# SCH_kxmx_kaugummi_4_0_2021-10-22.net
KiCad netlist of a schematic drawn in EasyEDA
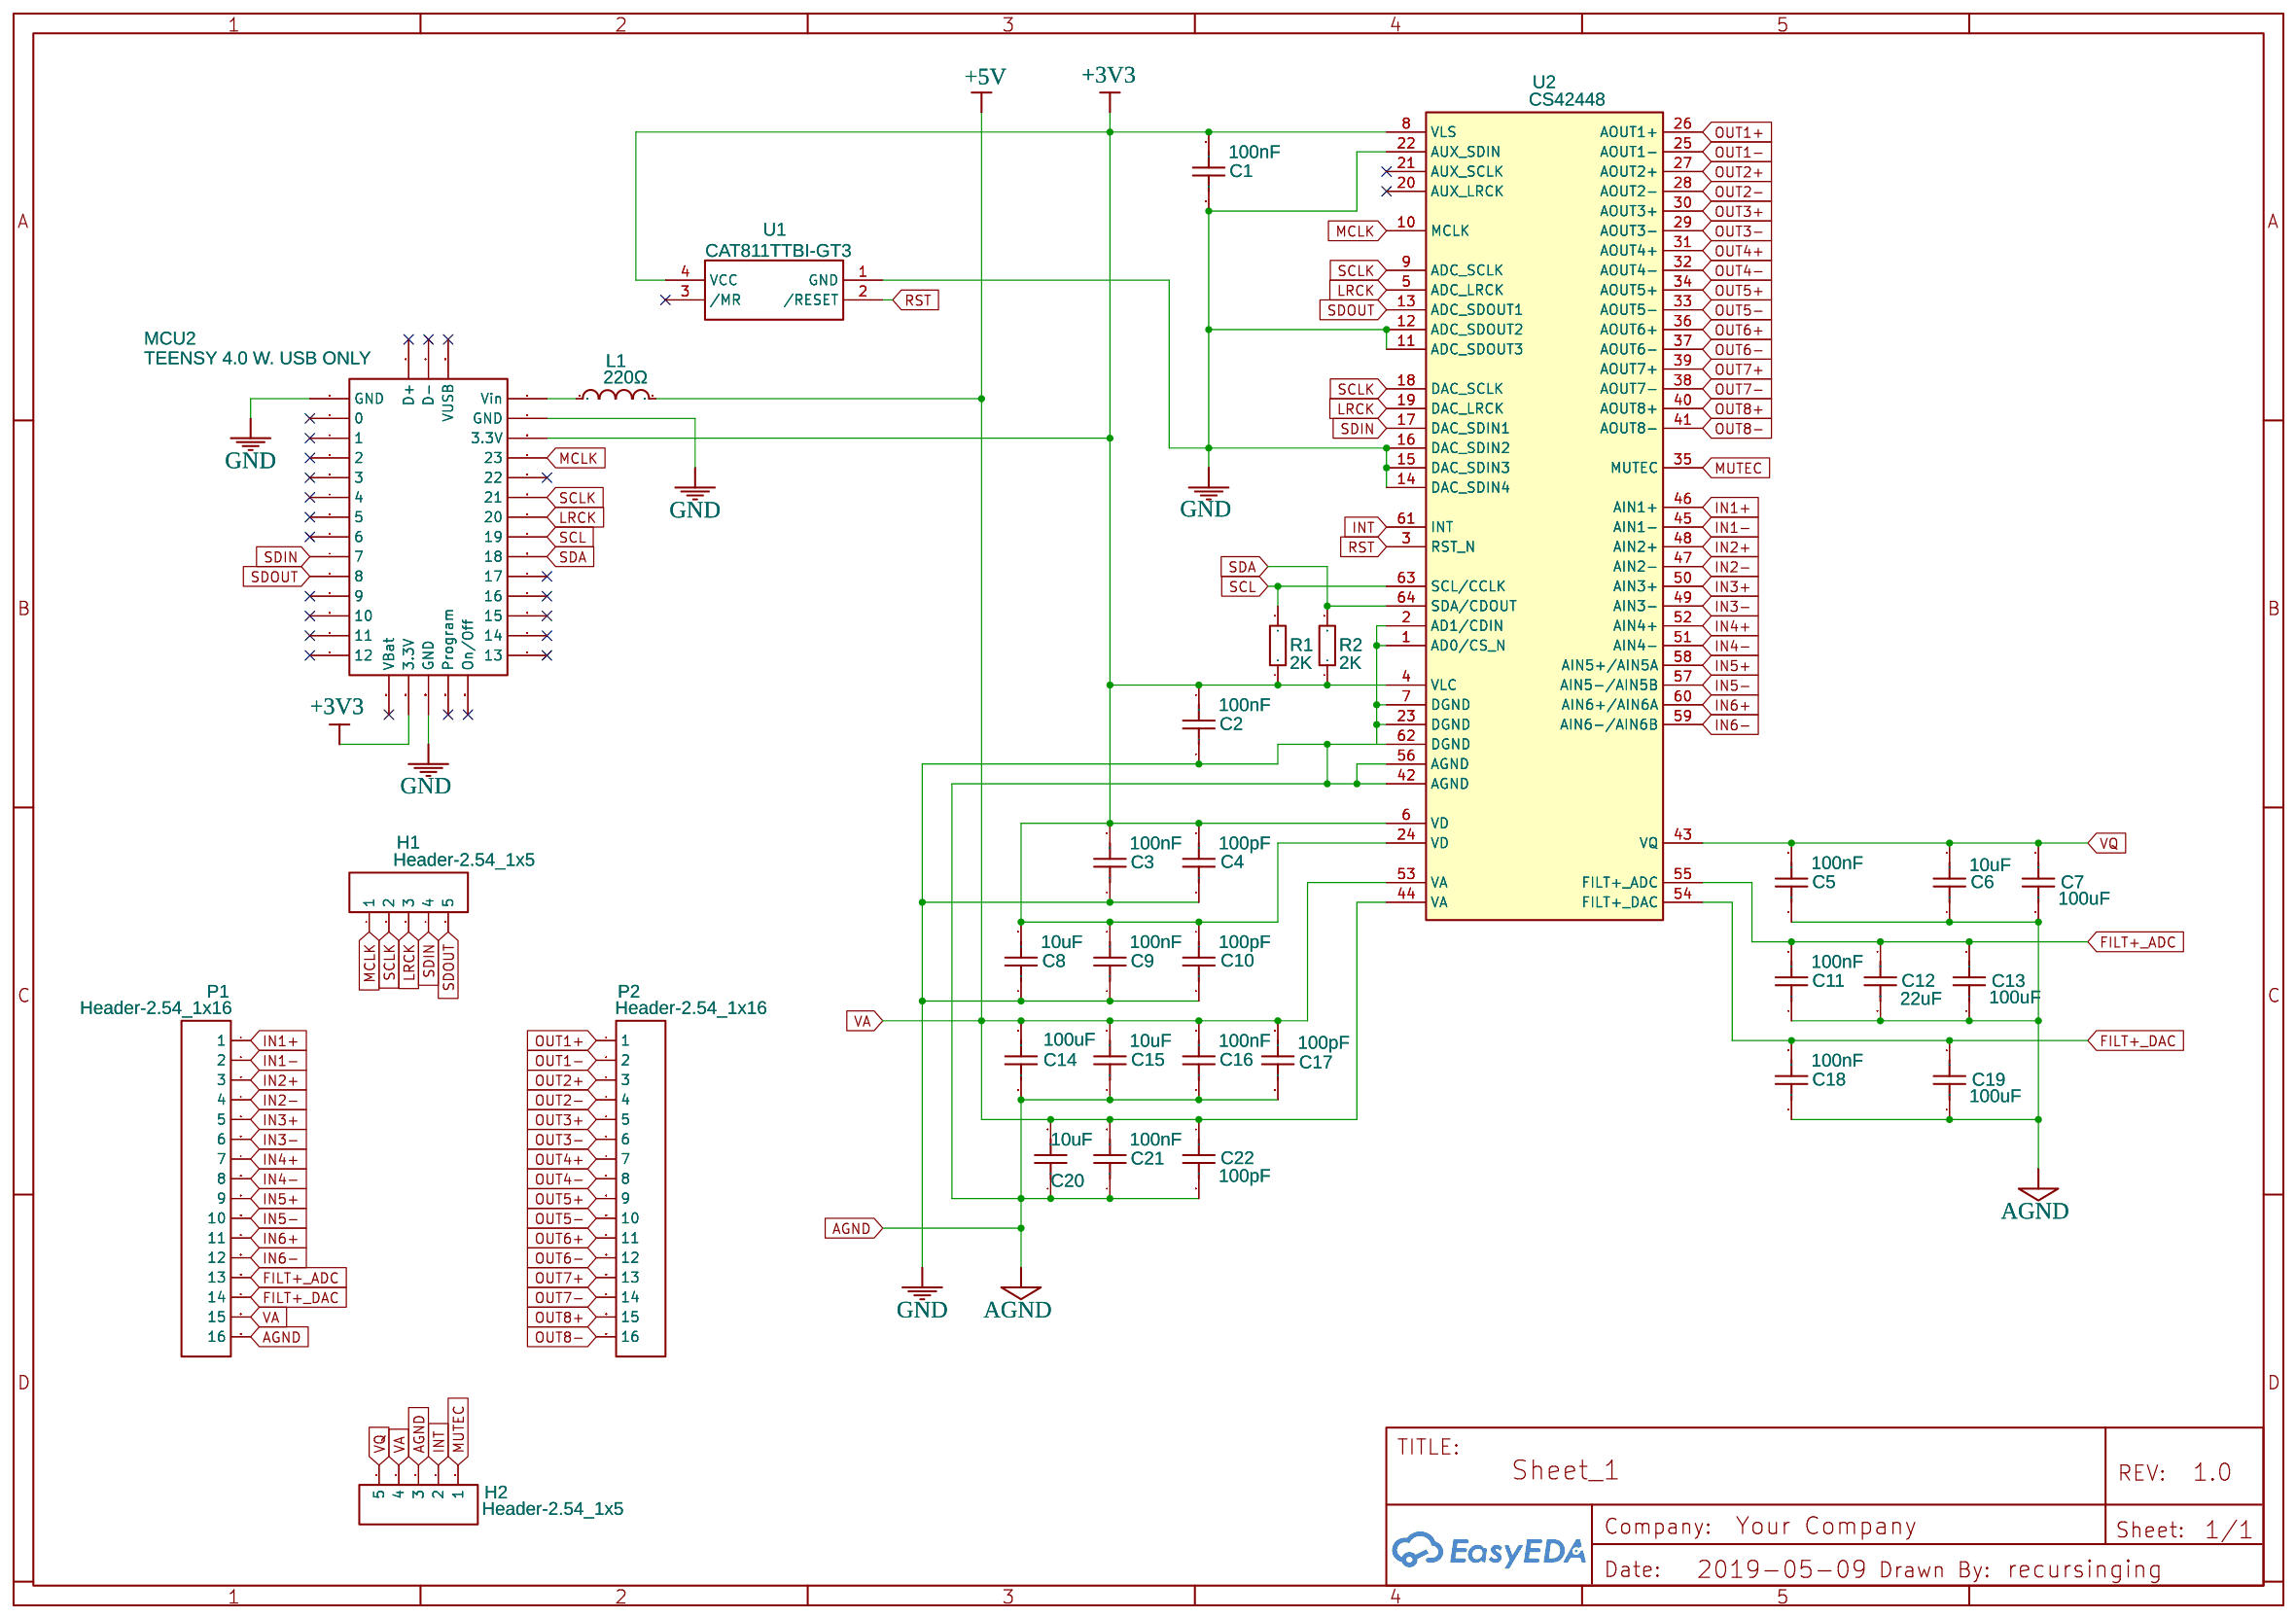
[diagram p0: schematic sheet]

(export (version "E")
  (design (tool "Eeschema 10.0.6"))
  (components
    (comp (ref "C1")
      (value "100nF")
      (fields
        (field (name "BOM_Manufacturer Part") "CL10B104KA8NNNC")
        (field (name "BOM_Supplier Part") "C1590")
      )
      (libsource (lib "") (part "CL10B104KA8NNNC"))
    )
    (comp (ref "C2")
      (value "100nF")
      (fields
        (field (name "BOM_Manufacturer Part") "CL10B104KA8NNNC")
        (field (name "BOM_Supplier Part") "C1590")
      )
      (libsource (lib "") (part "CL10B104KA8NNNC"))
    )
    (comp (ref "C3")
      (value "100nF")
      (fields
        (field (name "BOM_Manufacturer Part") "CL10B104KA8NNNC")
        (field (name "BOM_Supplier Part") "C1590")
      )
      (libsource (lib "") (part "CL10B104KA8NNNC"))
    )
    (comp (ref "C4")
      (value "100pF")
      (fields
        (field (name "BOM_Manufacturer Part") "0603B101K500CT")
        (field (name "BOM_Supplier Part") "C338150")
      )
      (libsource (lib "") (part "0603B101K500CT"))
    )
    (comp (ref "C5")
      (value "100nF")
      (fields
        (field (name "BOM_Manufacturer Part") "CL10B104KA8NNNC")
        (field (name "BOM_Supplier Part") "C1590")
      )
      (libsource (lib "") (part "CL10B104KA8NNNC"))
    )
    (comp (ref "C6")
      (value "10uF")
      (fields
        (field (name "BOM_Manufacturer Part") "CL10A106MQ8NNNC")
        (field (name "BOM_Supplier Part") "C1691")
      )
      (libsource (lib "") (part "CL10A106MQ8NNNC"))
    )
    (comp (ref "C7")
      (value "100uF")
      (fields
        (field (name "BOM_Manufacturer Part") "GRM31CR60J107ME39L")
        (field (name "BOM_Supplier Part") "C77085")
      )
      (libsource (lib "") (part "GRM31CR60J107ME39L"))
    )
    (comp (ref "C8")
      (value "10uF")
      (fields
        (field (name "BOM_Manufacturer Part") "CL10A106MQ8NNNC")
        (field (name "BOM_Supplier Part") "C1691")
      )
      (libsource (lib "") (part "CL10A106MQ8NNNC"))
    )
    (comp (ref "C9")
      (value "100nF")
      (fields
        (field (name "BOM_Manufacturer Part") "CL10B104KA8NNNC")
        (field (name "BOM_Supplier Part") "C1590")
      )
      (libsource (lib "") (part "CL10B104KA8NNNC"))
    )
    (comp (ref "C10")
      (value "100pF")
      (fields
        (field (name "BOM_Manufacturer Part") "0603B101K500CT")
        (field (name "BOM_Supplier Part") "C338150")
      )
      (libsource (lib "") (part "0603B101K500CT"))
    )
    (comp (ref "C11")
      (value "100nF")
      (fields
        (field (name "BOM_Manufacturer Part") "CL10B104KA8NNNC")
        (field (name "BOM_Supplier Part") "C1590")
      )
      (libsource (lib "") (part "CL10B104KA8NNNC"))
    )
    (comp (ref "C12")
      (value "22uF")
      (fields
        (field (name "BOM_Manufacturer Part") "CL10A226MQ8NRNE")
        (field (name "BOM_Supplier Part") "C159801")
      )
      (libsource (lib "") (part "CL10A226MQ8NRNE"))
    )
    (comp (ref "C13")
      (value "100uF")
      (fields
        (field (name "BOM_Manufacturer Part") "GRM31CR60J107ME39L")
        (field (name "BOM_Supplier Part") "C77085")
      )
      (libsource (lib "") (part "GRM31CR60J107ME39L"))
    )
    (comp (ref "C14")
      (value "100uF")
      (fields
        (field (name "BOM_Manufacturer Part") "GRM31CR60J107ME39L")
        (field (name "BOM_Supplier Part") "C77085")
      )
      (libsource (lib "") (part "GRM31CR60J107ME39L"))
    )
    (comp (ref "C15")
      (value "10uF")
      (fields
        (field (name "BOM_Manufacturer Part") "CL10A106MQ8NNNC")
        (field (name "BOM_Supplier Part") "C1691")
      )
      (libsource (lib "") (part "CL10A106MQ8NNNC"))
    )
    (comp (ref "C16")
      (value "100nF")
      (fields
        (field (name "BOM_Manufacturer Part") "CL10B104KA8NNNC")
        (field (name "BOM_Supplier Part") "C1590")
      )
      (libsource (lib "") (part "CL10B104KA8NNNC"))
    )
    (comp (ref "C17")
      (value "100pF")
      (fields
        (field (name "BOM_Manufacturer Part") "0603B101K500CT")
        (field (name "BOM_Supplier Part") "C338150")
      )
      (libsource (lib "") (part "0603B101K500CT"))
    )
    (comp (ref "C18")
      (value "100nF")
      (fields
        (field (name "BOM_Manufacturer Part") "CL10B104KA8NNNC")
        (field (name "BOM_Supplier Part") "C1590")
      )
      (libsource (lib "") (part "CL10B104KA8NNNC"))
    )
    (comp (ref "C19")
      (value "100uF")
      (fields
        (field (name "BOM_Manufacturer Part") "GRM31CR60J107ME39L")
        (field (name "BOM_Supplier Part") "C77085")
      )
      (libsource (lib "") (part "GRM31CR60J107ME39L"))
    )
    (comp (ref "C20")
      (value "10uF")
      (fields
        (field (name "BOM_Manufacturer Part") "CL10A106MQ8NNNC")
        (field (name "BOM_Supplier Part") "C1691")
      )
      (libsource (lib "") (part "CL10A106MQ8NNNC"))
    )
    (comp (ref "C21")
      (value "100nF")
      (fields
        (field (name "BOM_Manufacturer Part") "CL10B104KA8NNNC")
        (field (name "BOM_Supplier Part") "C1590")
      )
      (libsource (lib "") (part "CL10B104KA8NNNC"))
    )
    (comp (ref "C22")
      (value "100pF")
      (fields
        (field (name "BOM_Manufacturer Part") "0603B101K500CT")
        (field (name "BOM_Supplier Part") "C338150")
      )
      (libsource (lib "") (part "0603B101K500CT"))
    )
    (comp (ref "H1")
      (value "Header-2.54_1x5")
      (fields
        (field (name "BOM_Manufacturer Part") "2.54mm 1*5p Female header")
        (field (name "BOM_Supplier Part") "C50950")
      )
      (libsource (lib "") (part "Unknown_200_450"))
    )
    (comp (ref "H2")
      (value "Header-2.54_1x5")
      (fields
        (field (name "BOM_Manufacturer Part") "2.54mm 1*5p Female header")
        (field (name "BOM_Supplier Part") "C50950")
      )
      (libsource (lib "") (part "Unknown_205_750"))
    )
    (comp (ref "L1")
      (value "220Ω")
      (fields
        (field (name "BOM_Manufacturer Part") "BLM21PG221SH1D")
        (field (name "BOM_Supplier Part") "C88994")
      )
      (libsource (lib "") (part "BLM21PG221SH1D"))
    )
    (comp (ref "MCU2") (value "TEENSY 4.0 W. USB ONLY") (libsource (lib "") (part "Unknown_210_255")))
    (comp (ref "P1")
      (value "Header-2.54_1x16")
      (fields
        (field (name "BOM_Manufacturer Part") "Female header1*16P pitch 2.54mm")
        (field (name "BOM_Supplier Part") "C66987")
      )
      (libsource (lib "") (part "Unknown_100_595"))
    )
    (comp (ref "P2")
      (value "Header-2.54_1x16")
      (fields
        (field (name "BOM_Manufacturer Part") "Female header1*16P pitch 2.54mm")
        (field (name "BOM_Supplier Part") "C66987")
      )
      (libsource (lib "") (part "Unknown_315_595"))
    )
    (comp (ref "R1")
      (value "2K")
      (fields
        (field (name "BOM_Manufacturer Part") "RTT03202JTP")
        (field (name "BOM_Supplier Part") "C103396")
      )
      (libsource (lib "") (part "RTT03202JTP"))
    )
    (comp (ref "R2")
      (value "2K")
      (fields
        (field (name "BOM_Manufacturer Part") "RTT03202JTP")
        (field (name "BOM_Supplier Part") "C103396")
      )
      (libsource (lib "") (part "RTT03202JTP"))
    )
    (comp (ref "U1")
      (value "CAT811TTBI-GT3")
      (fields (field (name "BOM_Supplier Part") "C73274"))
      (libsource (lib "") (part "Unknown_385_140"))
    )
    (comp (ref "U2")
      (value "CS42448")
      (fields (field (name "BOM_Manufacturer Part") "?"))
      (libsource (lib "") (part "Unknown_775_260"))
    )
  )
  (nets
    (net (code "1") (name "+3V3") (class "Default")
      (node (ref "C1") (pin "2") (pinfunction "2_2") (pintype "unspecified"))
      (node (ref "C10") (pin "1") (pinfunction "1_1") (pintype "unspecified"))
      (node (ref "C2") (pin "2") (pinfunction "2_2") (pintype "unspecified"))
      (node (ref "C3") (pin "2") (pinfunction "2_2") (pintype "unspecified"))
      (node (ref "C4") (pin "1") (pinfunction "1_1") (pintype "unspecified"))
      (node (ref "C8") (pin "2") (pinfunction "2_2") (pintype "unspecified"))
      (node (ref "C9") (pin "2") (pinfunction "2_2") (pintype "unspecified"))
      (node (ref "MCU2") (pin "3V30") (pinfunction "3.3V_3V30") (pintype "unspecified"))
      (node (ref "MCU2") (pin "3V31") (pinfunction "3.3V_3V31") (pintype "unspecified"))
      (node (ref "R1") (pin "1") (pinfunction "1_1") (pintype "input"))
      (node (ref "R2") (pin "1") (pinfunction "1_1") (pintype "input"))
      (node (ref "U1") (pin "4") (pinfunction "VCC_4") (pintype "unspecified"))
      (node (ref "U2") (pin "24") (pinfunction "VD_24") (pintype "passive"))
      (node (ref "U2") (pin "4") (pinfunction "VLC_4") (pintype "passive"))
      (node (ref "U2") (pin "6") (pinfunction "VD_6") (pintype "passive"))
      (node (ref "U2") (pin "8") (pinfunction "VLS_8") (pintype "bidirectional"))
    )
    (net (code "2") (name "AGND") (class "Default")
      (node (ref "C1") (pin "1") (pinfunction "1_1") (pintype "unspecified"))
      (node (ref "C10") (pin "2") (pinfunction "2_2") (pintype "unspecified"))
      (node (ref "C11") (pin "1") (pinfunction "1_1") (pintype "unspecified"))
      (node (ref "C12") (pin "2") (pinfunction "2_2") (pintype "unspecified"))
      (node (ref "C13") (pin "1") (pinfunction "1_1") (pintype "unspecified"))
      (node (ref "C14") (pin "1") (pinfunction "1_1") (pintype "unspecified"))
      (node (ref "C15") (pin "1") (pinfunction "1_1") (pintype "unspecified"))
      (node (ref "C16") (pin "1") (pinfunction "1_1") (pintype "unspecified"))
      (node (ref "C17") (pin "2") (pinfunction "2_2") (pintype "unspecified"))
      (node (ref "C18") (pin "1") (pinfunction "1_1") (pintype "unspecified"))
      (node (ref "C19") (pin "1") (pinfunction "1_1") (pintype "unspecified"))
      (node (ref "C2") (pin "1") (pinfunction "1_1") (pintype "unspecified"))
      (node (ref "C20") (pin "1") (pinfunction "1_1") (pintype "unspecified"))
      (node (ref "C21") (pin "1") (pinfunction "1_1") (pintype "unspecified"))
      (node (ref "C22") (pin "2") (pinfunction "2_2") (pintype "unspecified"))
      (node (ref "C3") (pin "1") (pinfunction "1_1") (pintype "unspecified"))
      (node (ref "C4") (pin "2") (pinfunction "2_2") (pintype "unspecified"))
      (node (ref "C5") (pin "1") (pinfunction "1_1") (pintype "unspecified"))
      (node (ref "C6") (pin "1") (pinfunction "1_1") (pintype "unspecified"))
      (node (ref "C7") (pin "1") (pinfunction "1_1") (pintype "unspecified"))
      (node (ref "C8") (pin "1") (pinfunction "1_1") (pintype "unspecified"))
      (node (ref "C9") (pin "1") (pinfunction "1_1") (pintype "unspecified"))
      (node (ref "H2") (pin "3") (pinfunction "3_3") (pintype "input"))
      (node (ref "MCU2") (pin "GND0") (pinfunction "GND_GND0") (pintype "unspecified"))
      (node (ref "MCU2") (pin "GND1") (pinfunction "GND_GND1") (pintype "unspecified"))
      (node (ref "MCU2") (pin "GND2") (pinfunction "GND_GND2") (pintype "unspecified"))
      (node (ref "P1") (pin "16") (pinfunction "16_16") (pintype "input"))
      (node (ref "U1") (pin "1") (pinfunction "GND_1") (pintype "unspecified"))
      (node (ref "U2") (pin "1") (pinfunction "AD0/CS_N_1") (pintype "passive"))
      (node (ref "U2") (pin "11") (pinfunction "ADC_SDOUT3_11") (pintype "bidirectional"))
      (node (ref "U2") (pin "12") (pinfunction "ADC_SDOUT2_12") (pintype "bidirectional"))
      (node (ref "U2") (pin "14") (pinfunction "DAC_SDIN4_14") (pintype "unspecified"))
      (node (ref "U2") (pin "15") (pinfunction "DAC_SDIN3_15") (pintype "unspecified"))
      (node (ref "U2") (pin "16") (pinfunction "DAC_SDIN2_16") (pintype "bidirectional"))
      (node (ref "U2") (pin "2") (pinfunction "AD1/CDIN_2") (pintype "unspecified"))
      (node (ref "U2") (pin "22") (pinfunction "AUX_SDIN_22") (pintype "bidirectional"))
      (node (ref "U2") (pin "23") (pinfunction "DGND_23") (pintype "passive"))
      (node (ref "U2") (pin "42") (pinfunction "AGND_42") (pintype "passive"))
      (node (ref "U2") (pin "56") (pinfunction "AGND_56") (pintype "passive"))
      (node (ref "U2") (pin "62") (pinfunction "DGND_62") (pintype "passive"))
      (node (ref "U2") (pin "7") (pinfunction "DGND_7") (pintype "passive"))
    )
    (net (code "3") (name "FILT+_ADC") (class "Default")
      (node (ref "C11") (pin "2") (pinfunction "2_2") (pintype "unspecified"))
      (node (ref "C12") (pin "1") (pinfunction "1_1") (pintype "unspecified"))
      (node (ref "C13") (pin "2") (pinfunction "2_2") (pintype "unspecified"))
      (node (ref "P1") (pin "13") (pinfunction "13_13") (pintype "input"))
      (node (ref "U2") (pin "55") (pinfunction "FILT+_ADC_55") (pintype "passive"))
    )
    (net (code "4") (name "FILT+_DAC") (class "Default")
      (node (ref "C18") (pin "2") (pinfunction "2_2") (pintype "unspecified"))
      (node (ref "C19") (pin "2") (pinfunction "2_2") (pintype "unspecified"))
      (node (ref "P1") (pin "14") (pinfunction "14_14") (pintype "input"))
      (node (ref "U2") (pin "54") (pinfunction "FILT+_DAC_54") (pintype "passive"))
    )
    (net (code "5") (name "IN1+") (class "Default")
      (node (ref "P1") (pin "1") (pinfunction "1_1") (pintype "input"))
      (node (ref "U2") (pin "46") (pinfunction "AIN1+_46") (pintype "bidirectional"))
    )
    (net (code "6") (name "IN1-") (class "Default")
      (node (ref "P1") (pin "2") (pinfunction "2_2") (pintype "input"))
      (node (ref "U2") (pin "45") (pinfunction "AIN1-_45") (pintype "bidirectional"))
    )
    (net (code "7") (name "IN2+") (class "Default")
      (node (ref "P1") (pin "3") (pinfunction "3_3") (pintype "input"))
      (node (ref "U2") (pin "48") (pinfunction "AIN2+_48") (pintype "unspecified"))
    )
    (net (code "8") (name "IN2-") (class "Default")
      (node (ref "P1") (pin "4") (pinfunction "4_4") (pintype "input"))
      (node (ref "U2") (pin "47") (pinfunction "AIN2-_47") (pintype "unspecified"))
    )
    (net (code "9") (name "IN3+") (class "Default")
      (node (ref "P1") (pin "5") (pinfunction "5_5") (pintype "input"))
      (node (ref "U2") (pin "50") (pinfunction "AIN3+_50") (pintype "bidirectional"))
    )
    (net (code "10") (name "IN3-") (class "Default")
      (node (ref "P1") (pin "6") (pinfunction "6_6") (pintype "input"))
      (node (ref "U2") (pin "49") (pinfunction "AIN3-_49") (pintype "unspecified"))
    )
    (net (code "11") (name "IN4+") (class "Default")
      (node (ref "P1") (pin "7") (pinfunction "7_7") (pintype "input"))
      (node (ref "U2") (pin "52") (pinfunction "AIN4+_52") (pintype "unspecified"))
    )
    (net (code "12") (name "IN4-") (class "Default")
      (node (ref "P1") (pin "8") (pinfunction "8_8") (pintype "input"))
      (node (ref "U2") (pin "51") (pinfunction "AIN4-_51") (pintype "unspecified"))
    )
    (net (code "13") (name "IN5+") (class "Default")
      (node (ref "P1") (pin "9") (pinfunction "9_9") (pintype "input"))
      (node (ref "U2") (pin "58") (pinfunction "AIN5+/AIN5A_58") (pintype "passive"))
    )
    (net (code "14") (name "IN5-") (class "Default")
      (node (ref "P1") (pin "10") (pinfunction "10_10") (pintype "input"))
      (node (ref "U2") (pin "57") (pinfunction "AIN5-/AIN5B_57") (pintype "passive"))
    )
    (net (code "15") (name "IN6+") (class "Default")
      (node (ref "P1") (pin "11") (pinfunction "11_11") (pintype "input"))
      (node (ref "U2") (pin "60") (pinfunction "AIN6+/AIN6A_60") (pintype "passive"))
    )
    (net (code "16") (name "IN6-") (class "Default")
      (node (ref "P1") (pin "12") (pinfunction "12_12") (pintype "input"))
      (node (ref "U2") (pin "59") (pinfunction "AIN6-/AIN6B_59") (pintype "passive"))
    )
    (net (code "17") (name "INT") (class "Default")
      (node (ref "H2") (pin "2") (pinfunction "2_2") (pintype "input"))
      (node (ref "U2") (pin "61") (pinfunction "INT_61") (pintype "unspecified"))
    )
    (net (code "18") (name "LRCK") (class "Default")
      (node (ref "H1") (pin "3") (pinfunction "3_3") (pintype "input"))
      (node (ref "MCU2") (pin "20") (pinfunction "20_20") (pintype "unspecified"))
      (node (ref "U2") (pin "19") (pinfunction "DAC_LRCK_19") (pintype "bidirectional"))
      (node (ref "U2") (pin "5") (pinfunction "ADC_LRCK_5") (pintype "bidirectional"))
    )
    (net (code "19") (name "MCLK") (class "Default")
      (node (ref "H1") (pin "1") (pinfunction "1_1") (pintype "input"))
      (node (ref "MCU2") (pin "23") (pinfunction "23_23") (pintype "unspecified"))
      (node (ref "U2") (pin "10") (pinfunction "MCLK_10") (pintype "bidirectional"))
    )
    (net (code "20") (name "MUTEC") (class "Default")
      (node (ref "H2") (pin "1") (pinfunction "1_1") (pintype "input"))
      (node (ref "U2") (pin "35") (pinfunction "MUTEC_35") (pintype "bidirectional"))
    )
    (net (code "21") (name "Net-(MCU2-Vin)") (class "Default")
      (node (ref "L1") (pin "1") (pinfunction "1_1") (pintype "unspecified"))
      (node (ref "MCU2") (pin "VIN") (pinfunction "Vin_VIN") (pintype "unspecified"))
    )
    (net (code "22") (name "OUT1+") (class "Default")
      (node (ref "P2") (pin "1") (pinfunction "1_1") (pintype "input"))
      (node (ref "U2") (pin "26") (pinfunction "AOUT1+_26") (pintype "bidirectional"))
    )
    (net (code "23") (name "OUT1-") (class "Default")
      (node (ref "P2") (pin "2") (pinfunction "2_2") (pintype "input"))
      (node (ref "U2") (pin "25") (pinfunction "AOUT1-_25") (pintype "bidirectional"))
    )
    (net (code "24") (name "OUT2+") (class "Default")
      (node (ref "P2") (pin "3") (pinfunction "3_3") (pintype "input"))
      (node (ref "U2") (pin "27") (pinfunction "AOUT2+_27") (pintype "bidirectional"))
    )
    (net (code "25") (name "OUT2-") (class "Default")
      (node (ref "P2") (pin "4") (pinfunction "4_4") (pintype "input"))
      (node (ref "U2") (pin "28") (pinfunction "AOUT2-_28") (pintype "bidirectional"))
    )
    (net (code "26") (name "OUT3+") (class "Default")
      (node (ref "P2") (pin "5") (pinfunction "5_5") (pintype "input"))
      (node (ref "U2") (pin "30") (pinfunction "AOUT3+_30") (pintype "bidirectional"))
    )
    (net (code "27") (name "OUT3-") (class "Default")
      (node (ref "P2") (pin "6") (pinfunction "6_6") (pintype "input"))
      (node (ref "U2") (pin "29") (pinfunction "AOUT3-_29") (pintype "bidirectional"))
    )
    (net (code "28") (name "OUT4+") (class "Default")
      (node (ref "P2") (pin "7") (pinfunction "7_7") (pintype "input"))
      (node (ref "U2") (pin "31") (pinfunction "AOUT4+_31") (pintype "bidirectional"))
    )
    (net (code "29") (name "OUT4-") (class "Default")
      (node (ref "P2") (pin "8") (pinfunction "8_8") (pintype "input"))
      (node (ref "U2") (pin "32") (pinfunction "AOUT4-_32") (pintype "bidirectional"))
    )
    (net (code "30") (name "OUT5+") (class "Default")
      (node (ref "P2") (pin "9") (pinfunction "9_9") (pintype "input"))
      (node (ref "U2") (pin "34") (pinfunction "AOUT5+_34") (pintype "bidirectional"))
    )
    (net (code "31") (name "OUT5-") (class "Default")
      (node (ref "P2") (pin "10") (pinfunction "10_10") (pintype "input"))
      (node (ref "U2") (pin "33") (pinfunction "AOUT5-_33") (pintype "bidirectional"))
    )
    (net (code "32") (name "OUT6+") (class "Default")
      (node (ref "P2") (pin "11") (pinfunction "11_11") (pintype "input"))
      (node (ref "U2") (pin "36") (pinfunction "AOUT6+_36") (pintype "bidirectional"))
    )
    (net (code "33") (name "OUT6-") (class "Default")
      (node (ref "P2") (pin "12") (pinfunction "12_12") (pintype "input"))
      (node (ref "U2") (pin "37") (pinfunction "AOUT6-_37") (pintype "bidirectional"))
    )
    (net (code "34") (name "OUT7+") (class "Default")
      (node (ref "P2") (pin "13") (pinfunction "13_13") (pintype "input"))
      (node (ref "U2") (pin "39") (pinfunction "AOUT7+_39") (pintype "bidirectional"))
    )
    (net (code "35") (name "OUT7-") (class "Default")
      (node (ref "P2") (pin "14") (pinfunction "14_14") (pintype "input"))
      (node (ref "U2") (pin "38") (pinfunction "AOUT7-_38") (pintype "bidirectional"))
    )
    (net (code "36") (name "OUT8+") (class "Default")
      (node (ref "P2") (pin "15") (pinfunction "15_15") (pintype "input"))
      (node (ref "U2") (pin "40") (pinfunction "AOUT8+_40") (pintype "bidirectional"))
    )
    (net (code "37") (name "OUT8-") (class "Default")
      (node (ref "P2") (pin "16") (pinfunction "16_16") (pintype "input"))
      (node (ref "U2") (pin "41") (pinfunction "AOUT8-_41") (pintype "bidirectional"))
    )
    (net (code "38") (name "RST") (class "Default")
      (node (ref "U1") (pin "2") (pinfunction "/RESET_2") (pintype "unspecified"))
      (node (ref "U2") (pin "3") (pinfunction "RST_N_3") (pintype "bidirectional"))
    )
    (net (code "39") (name "SCL") (class "Default")
      (node (ref "MCU2") (pin "19") (pinfunction "19_19") (pintype "unspecified"))
      (node (ref "R1") (pin "2") (pinfunction "2_2") (pintype "input"))
      (node (ref "U2") (pin "63") (pinfunction "SCL/CCLK_63") (pintype "bidirectional"))
    )
    (net (code "40") (name "SCLK") (class "Default")
      (node (ref "H1") (pin "2") (pinfunction "2_2") (pintype "input"))
      (node (ref "MCU2") (pin "21") (pinfunction "21_21") (pintype "unspecified"))
      (node (ref "U2") (pin "18") (pinfunction "DAC_SCLK_18") (pintype "bidirectional"))
      (node (ref "U2") (pin "9") (pinfunction "ADC_SCLK_9") (pintype "bidirectional"))
    )
    (net (code "41") (name "SDA") (class "Default")
      (node (ref "MCU2") (pin "18") (pinfunction "18_18") (pintype "unspecified"))
      (node (ref "R2") (pin "2") (pinfunction "2_2") (pintype "input"))
      (node (ref "U2") (pin "64") (pinfunction "SDA/CDOUT_64") (pintype "unspecified"))
    )
    (net (code "42") (name "SDIN") (class "Default")
      (node (ref "H1") (pin "4") (pinfunction "4_4") (pintype "input"))
      (node (ref "MCU2") (pin "7") (pinfunction "7_7") (pintype "unspecified"))
      (node (ref "U2") (pin "17") (pinfunction "DAC_SDIN1_17") (pintype "bidirectional"))
    )
    (net (code "43") (name "SDOUT") (class "Default")
      (node (ref "H1") (pin "5") (pinfunction "5_5") (pintype "input"))
      (node (ref "MCU2") (pin "8") (pinfunction "8_8") (pintype "unspecified"))
      (node (ref "U2") (pin "13") (pinfunction "ADC_SDOUT1_13") (pintype "bidirectional"))
    )
    (net (code "44") (name "VA") (class "Default")
      (node (ref "C14") (pin "2") (pinfunction "2_2") (pintype "unspecified"))
      (node (ref "C15") (pin "2") (pinfunction "2_2") (pintype "unspecified"))
      (node (ref "C16") (pin "2") (pinfunction "2_2") (pintype "unspecified"))
      (node (ref "C17") (pin "1") (pinfunction "1_1") (pintype "unspecified"))
      (node (ref "C20") (pin "2") (pinfunction "2_2") (pintype "unspecified"))
      (node (ref "C21") (pin "2") (pinfunction "2_2") (pintype "unspecified"))
      (node (ref "C22") (pin "1") (pinfunction "1_1") (pintype "unspecified"))
      (node (ref "H2") (pin "4") (pinfunction "4_4") (pintype "input"))
      (node (ref "L1") (pin "2") (pinfunction "2_2") (pintype "unspecified"))
      (node (ref "P1") (pin "15") (pinfunction "15_15") (pintype "input"))
      (node (ref "U2") (pin "44") (pinfunction "VA_44") (pintype "passive"))
      (node (ref "U2") (pin "53") (pinfunction "VA_53") (pintype "passive"))
    )
    (net (code "45") (name "VQ") (class "Default")
      (node (ref "C5") (pin "2") (pinfunction "2_2") (pintype "unspecified"))
      (node (ref "C6") (pin "2") (pinfunction "2_2") (pintype "unspecified"))
      (node (ref "C7") (pin "2") (pinfunction "2_2") (pintype "unspecified"))
      (node (ref "H2") (pin "5") (pinfunction "5_5") (pintype "input"))
      (node (ref "U2") (pin "43") (pinfunction "VQ_43") (pintype "passive"))
    )
    (net (code "46") (name "unconnected-(MCU2-On{slash}Off-PadONOFF)") (class "Default")
      (node (ref "MCU2") (pin "ONOFF") (pinfunction "On/Off_ONOFF") (pintype "unspecified+no_connect"))
    )
    (net (code "47") (name "unconnected-(MCU2-Pad0)") (class "Default")
      (node (ref "MCU2") (pin "0") (pinfunction "0_0") (pintype "unspecified+no_connect"))
    )
    (net (code "48") (name "unconnected-(MCU2-Pad1)") (class "Default")
      (node (ref "MCU2") (pin "1") (pinfunction "1_1") (pintype "unspecified+no_connect"))
    )
    (net (code "49") (name "unconnected-(MCU2-Pad2)") (class "Default")
      (node (ref "MCU2") (pin "2") (pinfunction "2_2") (pintype "unspecified+no_connect"))
    )
    (net (code "50") (name "unconnected-(MCU2-Pad3)") (class "Default")
      (node (ref "MCU2") (pin "3") (pinfunction "3_3") (pintype "unspecified+no_connect"))
    )
    (net (code "51") (name "unconnected-(MCU2-Pad4)") (class "Default")
      (node (ref "MCU2") (pin "4") (pinfunction "4_4") (pintype "unspecified+no_connect"))
    )
    (net (code "52") (name "unconnected-(MCU2-Pad5)") (class "Default")
      (node (ref "MCU2") (pin "5") (pinfunction "5_5") (pintype "unspecified+no_connect"))
    )
    (net (code "53") (name "unconnected-(MCU2-Pad6)") (class "Default")
      (node (ref "MCU2") (pin "6") (pinfunction "6_6") (pintype "unspecified+no_connect"))
    )
    (net (code "54") (name "unconnected-(MCU2-Pad9)") (class "Default")
      (node (ref "MCU2") (pin "9") (pinfunction "9_9") (pintype "unspecified+no_connect"))
    )
    (net (code "55") (name "unconnected-(MCU2-Pad10)") (class "Default")
      (node (ref "MCU2") (pin "10") (pinfunction "10_10") (pintype "unspecified+no_connect"))
    )
    (net (code "56") (name "unconnected-(MCU2-Pad11)") (class "Default")
      (node (ref "MCU2") (pin "11") (pinfunction "11_11") (pintype "unspecified+no_connect"))
    )
    (net (code "57") (name "unconnected-(MCU2-Pad12)") (class "Default")
      (node (ref "MCU2") (pin "12") (pinfunction "12_12") (pintype "unspecified+no_connect"))
    )
    (net (code "58") (name "unconnected-(MCU2-Pad13)") (class "Default")
      (node (ref "MCU2") (pin "13") (pinfunction "13_13") (pintype "unspecified+no_connect"))
    )
    (net (code "59") (name "unconnected-(MCU2-Pad14)") (class "Default")
      (node (ref "MCU2") (pin "14") (pinfunction "14_14") (pintype "unspecified+no_connect"))
    )
    (net (code "60") (name "unconnected-(MCU2-Pad15)") (class "Default")
      (node (ref "MCU2") (pin "15") (pinfunction "15_15") (pintype "unspecified+no_connect"))
    )
    (net (code "61") (name "unconnected-(MCU2-Pad16)") (class "Default")
      (node (ref "MCU2") (pin "16") (pinfunction "16_16") (pintype "unspecified+no_connect"))
    )
    (net (code "62") (name "unconnected-(MCU2-Pad17)") (class "Default")
      (node (ref "MCU2") (pin "17") (pinfunction "17_17") (pintype "unspecified+no_connect"))
    )
    (net (code "63") (name "unconnected-(MCU2-Pad22)") (class "Default")
      (node (ref "MCU2") (pin "22") (pinfunction "22_22") (pintype "unspecified+no_connect"))
    )
    (net (code "64") (name "unconnected-(MCU2-PadD+)") (class "Default")
      (node (ref "MCU2") (pin "D+") (pinfunction "D+_D+") (pintype "unspecified+no_connect"))
    )
    (net (code "65") (name "unconnected-(MCU2-PadD-)") (class "Default")
      (node (ref "MCU2") (pin "D-") (pinfunction "D-_D-") (pintype "unspecified+no_connect"))
    )
    (net (code "66") (name "unconnected-(MCU2-PadVUSB)") (class "Default")
      (node (ref "MCU2") (pin "VUSB") (pinfunction "VUSB_VUSB") (pintype "unspecified+no_connect"))
    )
    (net (code "67") (name "unconnected-(MCU2-Program-PadPRGM)") (class "Default")
      (node (ref "MCU2") (pin "PRGM") (pinfunction "Program_PRGM") (pintype "unspecified+no_connect"))
    )
    (net (code "68") (name "unconnected-(MCU2-VBat-PadVBAT)") (class "Default")
      (node (ref "MCU2") (pin "VBAT") (pinfunction "VBat_VBAT") (pintype "unspecified+no_connect"))
    )
    (net (code "69") (name "unconnected-(U1-{slash}MR-Pad3)") (class "Default")
      (node (ref "U1") (pin "3") (pinfunction "/MR_3") (pintype "unspecified+no_connect"))
    )
    (net (code "70") (name "unconnected-(U2-AUX_LRCK-Pad20)") (class "Default")
      (node (ref "U2") (pin "20") (pinfunction "AUX_LRCK_20") (pintype "bidirectional+no_connect"))
    )
    (net (code "71") (name "unconnected-(U2-AUX_SCLK-Pad21)") (class "Default")
      (node (ref "U2") (pin "21") (pinfunction "AUX_SCLK_21") (pintype "bidirectional+no_connect"))
    )
  )
)
